# stm32f7.net
KiCad netlist of a schematic drawn in EAGLE
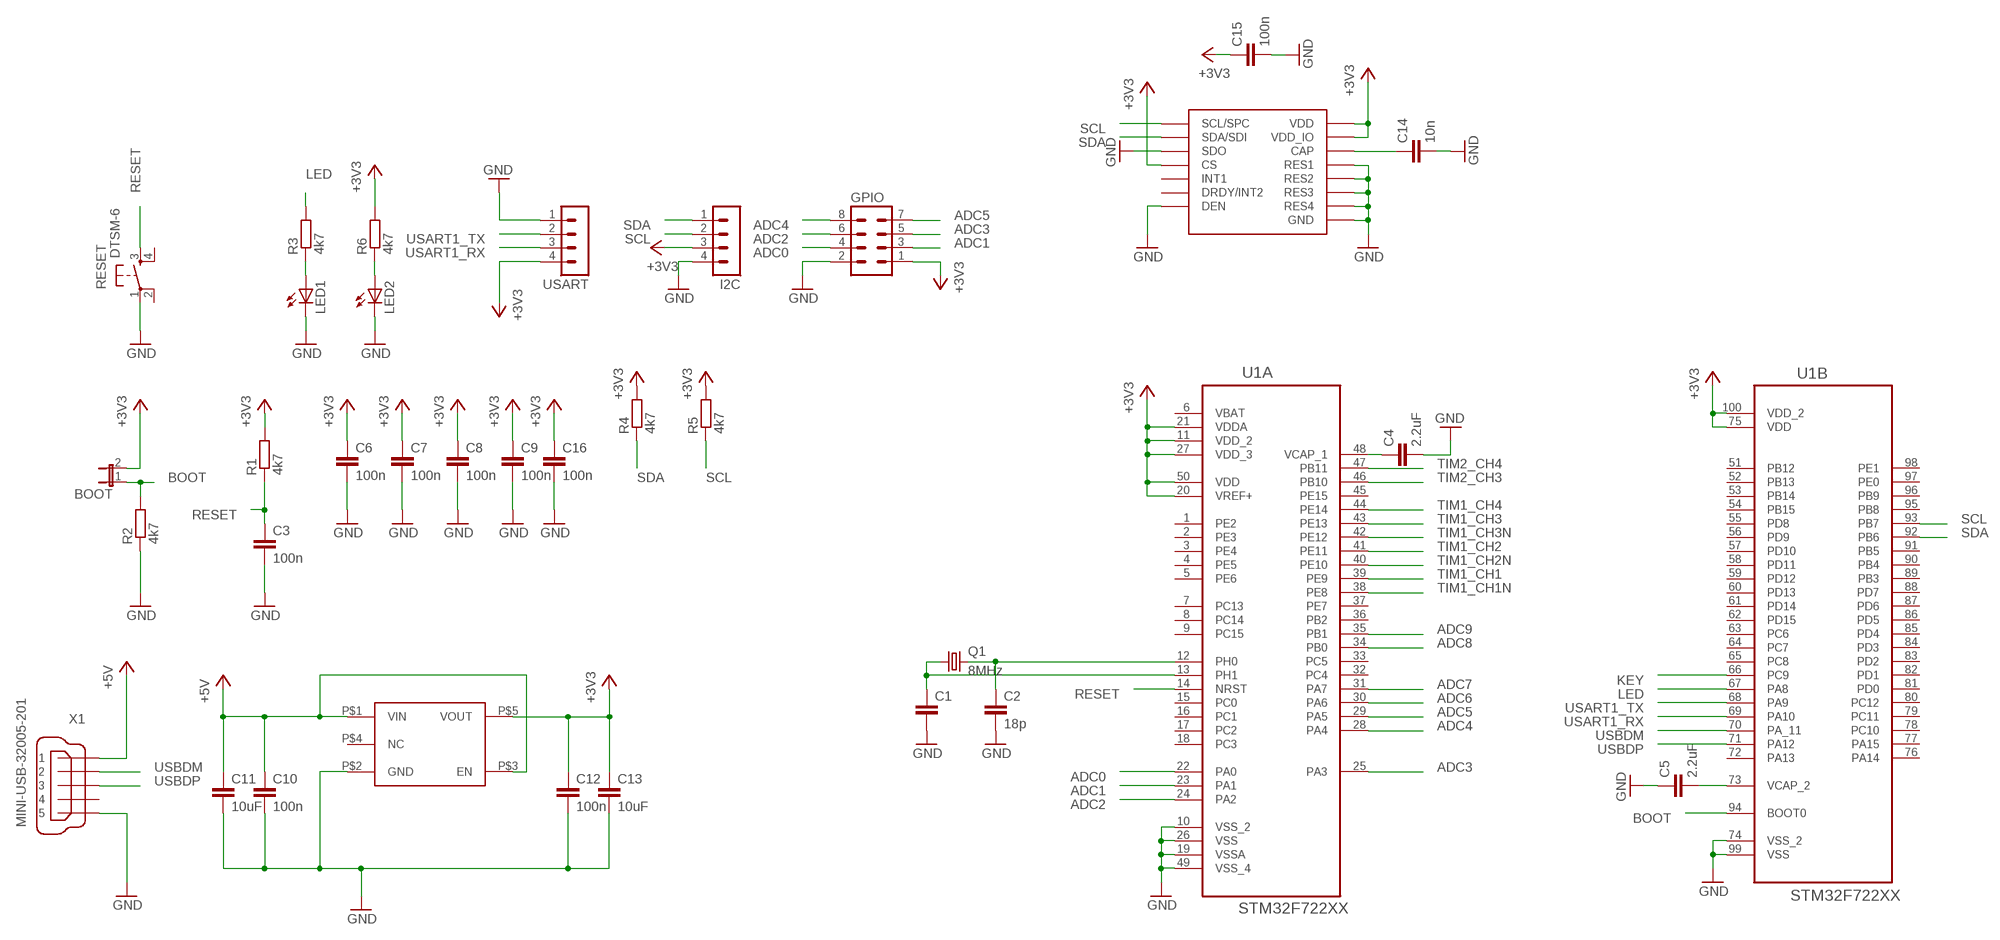
[diagram p0: schematic, sheet 1]

(export (version "E")
  (design (tool "Eeschema 10.0.6"))
  (components
    (comp (ref "BOOT")
      (value "JP1E")
      (footprint "eagle-import:JP1")
      (libsource (lib "eagle-import") (part "JP1E"))
    )
    (comp (ref "C1")
      (value "C-EUC0805")
      (footprint "eagle-import:C0805")
      (libsource (lib "eagle-import") (part "C-EUC0805"))
    )
    (comp (ref "C2")
      (value "18p")
      (footprint "eagle-import:C0805")
      (libsource (lib "eagle-import") (part "C-EUC0805"))
    )
    (comp (ref "C3")
      (value "100n")
      (footprint "eagle-import:C0805")
      (libsource (lib "eagle-import") (part "C-EUC0805"))
    )
    (comp (ref "C4")
      (value "2.2uF")
      (footprint "eagle-import:C0805")
      (libsource (lib "eagle-import") (part "C-EUC0805"))
    )
    (comp (ref "C5")
      (value "2.2uF")
      (footprint "eagle-import:C0805")
      (libsource (lib "eagle-import") (part "C-EUC0805"))
    )
    (comp (ref "C6")
      (value "100n")
      (footprint "eagle-import:C0805")
      (libsource (lib "eagle-import") (part "C-EUC0805"))
    )
    (comp (ref "C7")
      (value "100n")
      (footprint "eagle-import:C0805")
      (libsource (lib "eagle-import") (part "C-EUC0805"))
    )
    (comp (ref "C8")
      (value "100n")
      (footprint "eagle-import:C0805")
      (libsource (lib "eagle-import") (part "C-EUC0805"))
    )
    (comp (ref "C9")
      (value "100n")
      (footprint "eagle-import:C0805")
      (libsource (lib "eagle-import") (part "C-EUC0805"))
    )
    (comp (ref "C10")
      (value "100n")
      (footprint "eagle-import:C0805")
      (libsource (lib "eagle-import") (part "C-EUC0805"))
    )
    (comp (ref "C11")
      (value "10uF")
      (footprint "eagle-import:C0805")
      (libsource (lib "eagle-import") (part "C-EUC0805"))
    )
    (comp (ref "C12")
      (value "100n")
      (footprint "eagle-import:C0805")
      (libsource (lib "eagle-import") (part "C-EUC0805"))
    )
    (comp (ref "C13")
      (value "10uF")
      (footprint "eagle-import:C0805")
      (libsource (lib "eagle-import") (part "C-EUC0805"))
    )
    (comp (ref "C14")
      (value "10n")
      (footprint "eagle-import:C0805")
      (libsource (lib "eagle-import") (part "C-EUC0805"))
    )
    (comp (ref "C15")
      (value "100n")
      (footprint "eagle-import:C0805")
      (libsource (lib "eagle-import") (part "C-EUC0805"))
    )
    (comp (ref "C16")
      (value "100n")
      (footprint "eagle-import:C0805")
      (libsource (lib "eagle-import") (part "C-EUC0805"))
    )
    (comp (ref "GPIO")
      (value "MA04-2")
      (footprint "eagle-import:MA04-2")
      (libsource (lib "eagle-import") (part "MA04-2"))
    )
    (comp (ref "I2C")
      (value "MA04-1")
      (footprint "eagle-import:MA04-1")
      (libsource (lib "eagle-import") (part "MA04-1"))
    )
    (comp (ref "LED1")
      (value "LEDCHIPLED_1206")
      (footprint "eagle-import:CHIPLED_1206")
      (libsource (lib "eagle-import") (part "LEDCHIPLED_1206"))
    )
    (comp (ref "LED2")
      (value "LEDCHIPLED_1206")
      (footprint "eagle-import:CHIPLED_1206")
      (libsource (lib "eagle-import") (part "LEDCHIPLED_1206"))
    )
    (comp (ref "Q1")
      (value "8MHz")
      (footprint "eagle-import:CTS406")
      (libsource (lib "eagle-import") (part "CRYSTALCTS406"))
    )
    (comp (ref "R1")
      (value "4k7")
      (footprint "eagle-import:M0805")
      (libsource (lib "eagle-import") (part "R-EU_M0805"))
    )
    (comp (ref "R2")
      (value "4k7")
      (footprint "eagle-import:M0805")
      (libsource (lib "eagle-import") (part "R-EU_M0805"))
    )
    (comp (ref "R3")
      (value "4k7")
      (footprint "eagle-import:M0805")
      (libsource (lib "eagle-import") (part "R-EU_M0805"))
    )
    (comp (ref "R4")
      (value "4k7")
      (footprint "eagle-import:M0805")
      (libsource (lib "eagle-import") (part "R-EU_M0805"))
    )
    (comp (ref "R5")
      (value "4k7")
      (footprint "eagle-import:M0805")
      (libsource (lib "eagle-import") (part "R-EU_M0805"))
    )
    (comp (ref "R6")
      (value "4k7")
      (footprint "eagle-import:M0805")
      (libsource (lib "eagle-import") (part "R-EU_M0805"))
    )
    (comp (ref "RESET")
      (value "DTSM-6")
      (footprint "eagle-import:DTSM-6")
      (libsource (lib "eagle-import") (part "DTSM-6"))
    )
    (comp (ref "U$1")
      (value "MIC5504-3.3Y")
      (footprint "eagle-import:SOT23-5")
      (libsource (lib "eagle-import") (part "MIC5504-3.3Y"))
    )
    (comp (ref "U$2")
      (value "ST_L3GD20H")
      (footprint "eagle-import:ST_LGA16L")
      (libsource (lib "eagle-import") (part "ST_L3GD20H"))
    )
    (comp (ref "U1")
      (value "STM32F722XX")
      (footprint "eagle-import:QFP50P1600X1600X160-100N")
      (fields (field (name "MPN") "STM32F407VET6"))
      (libsource (lib "eagle-import") (part "STM32F722XX"))
    )
    (comp (ref "USART")
      (value "MA04-1")
      (footprint "eagle-import:MA04-1")
      (libsource (lib "eagle-import") (part "MA04-1"))
    )
    (comp (ref "X1")
      (value "MINI-USB-32005-201")
      (footprint "eagle-import:32005-201")
      (libsource (lib "eagle-import") (part "MINI-USB-32005-201"))
    )
  )
  (nets
    (net (code "1") (name "+3V3") (class "Default")
      (node (ref "BOOT") (pin "2") (pinfunction "2_2") (pintype "passive"))
      (node (ref "C12") (pin "1") (pinfunction "1_1") (pintype "passive"))
      (node (ref "C13") (pin "1") (pinfunction "1_1") (pintype "passive"))
      (node (ref "C15") (pin "1") (pinfunction "1_1") (pintype "passive"))
      (node (ref "C16") (pin "1") (pinfunction "1_1") (pintype "passive"))
      (node (ref "C6") (pin "1") (pinfunction "1_1") (pintype "passive"))
      (node (ref "C7") (pin "1") (pinfunction "1_1") (pintype "passive"))
      (node (ref "C8") (pin "1") (pinfunction "1_1") (pintype "passive"))
      (node (ref "C9") (pin "1") (pinfunction "1_1") (pintype "passive"))
      (node (ref "GPIO") (pin "1") (pinfunction "1_1") (pintype "passive"))
      (node (ref "I2C") (pin "3") (pinfunction "3_3") (pintype "passive"))
      (node (ref "R1") (pin "2") (pinfunction "2_2") (pintype "passive"))
      (node (ref "R4") (pin "2") (pinfunction "2_2") (pintype "passive"))
      (node (ref "R5") (pin "2") (pinfunction "2_2") (pintype "passive"))
      (node (ref "R6") (pin "2") (pinfunction "2_2") (pintype "passive"))
      (node (ref "U$1") (pin "P$5") (pinfunction "VOUT_P$5") (pintype "bidirectional"))
      (node (ref "U$2") (pin "P$1") (pinfunction "VDD_IO_P$1") (pintype "power_in"))
      (node (ref "U$2") (pin "P$16") (pinfunction "VDD_P$16") (pintype "power_in"))
      (node (ref "U$2") (pin "P$5") (pinfunction "CS_P$5") (pintype "bidirectional"))
      (node (ref "U1") (pin "100") (pinfunction "VDD_2_100") (pintype "power_in"))
      (node (ref "U1") (pin "11") (pinfunction "VDD_2_11") (pintype "power_in"))
      (node (ref "U1") (pin "20") (pinfunction "VREF+_20") (pintype "power_in"))
      (node (ref "U1") (pin "21") (pinfunction "VDDA_21") (pintype "power_in"))
      (node (ref "U1") (pin "27") (pinfunction "VDD_3_27") (pintype "power_in"))
      (node (ref "U1") (pin "50") (pinfunction "VDD_50") (pintype "power_in"))
      (node (ref "U1") (pin "75") (pinfunction "VDD_75") (pintype "power_in"))
      (node (ref "USART") (pin "4") (pinfunction "4_4") (pintype "passive"))
    )
    (net (code "2") (name "+5V") (class "Default")
      (node (ref "C10") (pin "1") (pinfunction "1_1") (pintype "passive"))
      (node (ref "C11") (pin "1") (pinfunction "1_1") (pintype "passive"))
      (node (ref "U$1") (pin "P$1") (pinfunction "VIN_P$1") (pintype "bidirectional"))
      (node (ref "U$1") (pin "P$3") (pinfunction "EN_P$3") (pintype "bidirectional"))
      (node (ref "X1") (pin "1") (pinfunction "1_1") (pintype "passive"))
    )
    (net (code "3") (name "/ADC0") (class "Default")
      (node (ref "GPIO") (pin "4") (pinfunction "4_4") (pintype "passive"))
      (node (ref "U1") (pin "22") (pinfunction "PA0_22") (pintype "bidirectional"))
    )
    (net (code "4") (name "/ADC1") (class "Default")
      (node (ref "GPIO") (pin "3") (pinfunction "3_3") (pintype "passive"))
      (node (ref "U1") (pin "23") (pinfunction "PA1_23") (pintype "bidirectional"))
    )
    (net (code "5") (name "/ADC2") (class "Default")
      (node (ref "GPIO") (pin "6") (pinfunction "6_6") (pintype "passive"))
      (node (ref "U1") (pin "24") (pinfunction "PA2_24") (pintype "bidirectional"))
    )
    (net (code "6") (name "/ADC3") (class "Default")
      (node (ref "GPIO") (pin "5") (pinfunction "5_5") (pintype "passive"))
      (node (ref "U1") (pin "25") (pinfunction "PA3_25") (pintype "bidirectional"))
    )
    (net (code "7") (name "/ADC4") (class "Default")
      (node (ref "GPIO") (pin "8") (pinfunction "8_8") (pintype "passive"))
      (node (ref "U1") (pin "28") (pinfunction "PA4_28") (pintype "bidirectional"))
    )
    (net (code "8") (name "/ADC5") (class "Default")
      (node (ref "GPIO") (pin "7") (pinfunction "7_7") (pintype "passive"))
      (node (ref "U1") (pin "29") (pinfunction "PA5_29") (pintype "bidirectional"))
    )
    (net (code "9") (name "/ADC6") (class "Default")
      (node (ref "U1") (pin "30") (pinfunction "PA6_30") (pintype "bidirectional"))
    )
    (net (code "10") (name "/ADC7") (class "Default")
      (node (ref "U1") (pin "31") (pinfunction "PA7_31") (pintype "bidirectional"))
    )
    (net (code "11") (name "/ADC8") (class "Default")
      (node (ref "U1") (pin "34") (pinfunction "PB0_34") (pintype "bidirectional"))
    )
    (net (code "12") (name "/ADC9") (class "Default")
      (node (ref "U1") (pin "35") (pinfunction "PB1_35") (pintype "bidirectional"))
    )
    (net (code "13") (name "/BOOT") (class "Default")
      (node (ref "BOOT") (pin "1") (pinfunction "1_1") (pintype "passive"))
      (node (ref "R2") (pin "2") (pinfunction "2_2") (pintype "passive"))
      (node (ref "U1") (pin "94") (pinfunction "BOOT0_94") (pintype "input"))
    )
    (net (code "14") (name "/KEY") (class "Default")
      (node (ref "U1") (pin "66") (pinfunction "PC9_66") (pintype "bidirectional"))
    )
    (net (code "15") (name "/LED") (class "Default")
      (node (ref "R3") (pin "2") (pinfunction "2_2") (pintype "passive"))
      (node (ref "U1") (pin "67") (pinfunction "PA8_67") (pintype "bidirectional"))
    )
    (net (code "16") (name "/RESET") (class "Default")
      (node (ref "C3") (pin "1") (pinfunction "1_1") (pintype "passive"))
      (node (ref "R1") (pin "1") (pinfunction "1_1") (pintype "passive"))
      (node (ref "RESET") (pin "3") (pinfunction "3_3") (pintype "passive"))
      (node (ref "U1") (pin "14") (pinfunction "NRST_14") (pintype "bidirectional"))
    )
    (net (code "17") (name "/SCL") (class "Default")
      (node (ref "I2C") (pin "2") (pinfunction "2_2") (pintype "passive"))
      (node (ref "R5") (pin "1") (pinfunction "1_1") (pintype "passive"))
      (node (ref "U$2") (pin "P$2") (pinfunction "SCL/SPC_P$2") (pintype "bidirectional"))
      (node (ref "U1") (pin "93") (pinfunction "PB7_93") (pintype "bidirectional"))
    )
    (net (code "18") (name "/SDA") (class "Default")
      (node (ref "I2C") (pin "1") (pinfunction "1_1") (pintype "passive"))
      (node (ref "R4") (pin "1") (pinfunction "1_1") (pintype "passive"))
      (node (ref "U$2") (pin "P$3") (pinfunction "SDA/SDI_P$3") (pintype "bidirectional"))
      (node (ref "U1") (pin "92") (pinfunction "PB6_92") (pintype "bidirectional"))
    )
    (net (code "19") (name "/TIM1_CH1") (class "Default")
      (node (ref "U1") (pin "39") (pinfunction "PE9_39") (pintype "bidirectional"))
    )
    (net (code "20") (name "/TIM1_CH1N") (class "Default")
      (node (ref "U1") (pin "38") (pinfunction "PE8_38") (pintype "bidirectional"))
    )
    (net (code "21") (name "/TIM1_CH2") (class "Default")
      (node (ref "U1") (pin "41") (pinfunction "PE11_41") (pintype "bidirectional"))
    )
    (net (code "22") (name "/TIM1_CH2N") (class "Default")
      (node (ref "U1") (pin "40") (pinfunction "PE10_40") (pintype "bidirectional"))
    )
    (net (code "23") (name "/TIM1_CH3") (class "Default")
      (node (ref "U1") (pin "43") (pinfunction "PE13_43") (pintype "bidirectional"))
    )
    (net (code "24") (name "/TIM1_CH3N") (class "Default")
      (node (ref "U1") (pin "42") (pinfunction "PE12_42") (pintype "bidirectional"))
    )
    (net (code "25") (name "/TIM1_CH4") (class "Default")
      (node (ref "U1") (pin "44") (pinfunction "PE14_44") (pintype "bidirectional"))
    )
    (net (code "26") (name "/TIM2_CH3") (class "Default")
      (node (ref "U1") (pin "46") (pinfunction "PB10_46") (pintype "bidirectional"))
    )
    (net (code "27") (name "/TIM2_CH4") (class "Default")
      (node (ref "U1") (pin "47") (pinfunction "PB11_47") (pintype "bidirectional"))
    )
    (net (code "28") (name "/USART1_RX") (class "Default")
      (node (ref "U1") (pin "69") (pinfunction "PA10_69") (pintype "bidirectional"))
      (node (ref "USART") (pin "3") (pinfunction "3_3") (pintype "passive"))
    )
    (net (code "29") (name "/USART1_TX") (class "Default")
      (node (ref "U1") (pin "68") (pinfunction "PA9_68") (pintype "bidirectional"))
      (node (ref "USART") (pin "2") (pinfunction "2_2") (pintype "passive"))
    )
    (net (code "30") (name "/USBDM") (class "Default")
      (node (ref "U1") (pin "70") (pinfunction "PA_11_70") (pintype "bidirectional"))
      (node (ref "X1") (pin "2") (pinfunction "2_2") (pintype "passive"))
    )
    (net (code "31") (name "/USBDP") (class "Default")
      (node (ref "U1") (pin "71") (pinfunction "PA12_71") (pintype "bidirectional"))
      (node (ref "X1") (pin "3") (pinfunction "3_3") (pintype "passive"))
    )
    (net (code "32") (name "/VBAT") (class "Default")
      (node (ref "U1") (pin "6") (pinfunction "VBAT_6") (pintype "power_in"))
    )
    (net (code "33") (name "GND") (class "Default")
      (node (ref "C1") (pin "2") (pinfunction "2_2") (pintype "passive"))
      (node (ref "C10") (pin "2") (pinfunction "2_2") (pintype "passive"))
      (node (ref "C11") (pin "2") (pinfunction "2_2") (pintype "passive"))
      (node (ref "C12") (pin "2") (pinfunction "2_2") (pintype "passive"))
      (node (ref "C13") (pin "2") (pinfunction "2_2") (pintype "passive"))
      (node (ref "C14") (pin "2") (pinfunction "2_2") (pintype "passive"))
      (node (ref "C15") (pin "2") (pinfunction "2_2") (pintype "passive"))
      (node (ref "C16") (pin "2") (pinfunction "2_2") (pintype "passive"))
      (node (ref "C2") (pin "2") (pinfunction "2_2") (pintype "passive"))
      (node (ref "C3") (pin "2") (pinfunction "2_2") (pintype "passive"))
      (node (ref "C4") (pin "2") (pinfunction "2_2") (pintype "passive"))
      (node (ref "C5") (pin "1") (pinfunction "1_1") (pintype "passive"))
      (node (ref "C6") (pin "2") (pinfunction "2_2") (pintype "passive"))
      (node (ref "C7") (pin "2") (pinfunction "2_2") (pintype "passive"))
      (node (ref "C8") (pin "2") (pinfunction "2_2") (pintype "passive"))
      (node (ref "C9") (pin "2") (pinfunction "2_2") (pintype "passive"))
      (node (ref "GPIO") (pin "2") (pinfunction "2_2") (pintype "passive"))
      (node (ref "I2C") (pin "4") (pinfunction "4_4") (pintype "passive"))
      (node (ref "LED1") (pin "C") (pinfunction "C_C") (pintype "passive"))
      (node (ref "LED2") (pin "C") (pinfunction "C_C") (pintype "passive"))
      (node (ref "R2") (pin "1") (pinfunction "1_1") (pintype "passive"))
      (node (ref "RESET") (pin "1") (pinfunction "1_1") (pintype "passive"))
      (node (ref "U$1") (pin "P$2") (pinfunction "GND_P$2") (pintype "bidirectional"))
      (node (ref "U$2") (pin "P$10") (pinfunction "RES2_P$10") (pintype "bidirectional"))
      (node (ref "U$2") (pin "P$11") (pinfunction "RES3_P$11") (pintype "bidirectional"))
      (node (ref "U$2") (pin "P$12") (pinfunction "GND_P$12") (pintype "power_in"))
      (node (ref "U$2") (pin "P$13") (pinfunction "GND_P$13") (pintype "power_in"))
      (node (ref "U$2") (pin "P$15") (pinfunction "RES4_P$15") (pintype "bidirectional"))
      (node (ref "U$2") (pin "P$4") (pinfunction "SDO_P$4") (pintype "bidirectional"))
      (node (ref "U$2") (pin "P$8") (pinfunction "DEN_P$8") (pintype "bidirectional"))
      (node (ref "U$2") (pin "P$9") (pinfunction "RES1_P$9") (pintype "bidirectional"))
      (node (ref "U1") (pin "10") (pinfunction "VSS_2_10") (pintype "passive"))
      (node (ref "U1") (pin "19") (pinfunction "VSSA_19") (pintype "passive"))
      (node (ref "U1") (pin "26") (pinfunction "VSS_26") (pintype "passive"))
      (node (ref "U1") (pin "49") (pinfunction "VSS_4_49") (pintype "power_in"))
      (node (ref "U1") (pin "74") (pinfunction "VSS_2_74") (pintype "passive"))
      (node (ref "U1") (pin "99") (pinfunction "VSS_99") (pintype "passive"))
      (node (ref "USART") (pin "1") (pinfunction "1_1") (pintype "passive"))
      (node (ref "X1") (pin "5") (pinfunction "5_5") (pintype "passive"))
    )
    (net (code "34") (name "Net-(LED1-PadA)") (class "Default")
      (node (ref "LED1") (pin "A") (pinfunction "A_A") (pintype "passive"))
      (node (ref "R3") (pin "1") (pinfunction "1_1") (pintype "passive"))
    )
    (net (code "35") (name "Net-(LED2-PadA)") (class "Default")
      (node (ref "LED2") (pin "A") (pinfunction "A_A") (pintype "passive"))
      (node (ref "R6") (pin "1") (pinfunction "1_1") (pintype "passive"))
    )
    (net (code "36") (name "Net-(Q1-2)") (class "Default")
      (node (ref "C2") (pin "1") (pinfunction "1_1") (pintype "passive"))
      (node (ref "Q1") (pin "3") (pinfunction "2_3") (pintype "passive"))
      (node (ref "U1") (pin "12") (pinfunction "PH0_12") (pintype "bidirectional"))
    )
    (net (code "37") (name "Net-(U$2-CAP)") (class "Default")
      (node (ref "C14") (pin "1") (pinfunction "1_1") (pintype "passive"))
      (node (ref "U$2") (pin "P$14") (pinfunction "CAP_P$14") (pintype "bidirectional"))
    )
    (net (code "38") (name "Net-(U1A-PH1)") (class "Default")
      (node (ref "C1") (pin "1") (pinfunction "1_1") (pintype "passive"))
      (node (ref "Q1") (pin "1") (pinfunction "1_1") (pintype "passive"))
      (node (ref "U1") (pin "13") (pinfunction "PH1_13") (pintype "bidirectional"))
    )
    (net (code "39") (name "Net-(U1A-VCAP_1)") (class "Default")
      (node (ref "C4") (pin "1") (pinfunction "1_1") (pintype "passive"))
      (node (ref "U1") (pin "48") (pinfunction "VCAP_1_48") (pintype "power_in"))
    )
    (net (code "40") (name "Net-(U1B-VCAP_2)") (class "Default")
      (node (ref "C5") (pin "2") (pinfunction "2_2") (pintype "passive"))
      (node (ref "U1") (pin "73") (pinfunction "VCAP_2_73") (pintype "power_in"))
    )
    (net (code "41") (name "unconnected-(RESET-Pad2)") (class "Default")
      (node (ref "RESET") (pin "2") (pinfunction "2_2") (pintype "passive"))
    )
    (net (code "42") (name "unconnected-(RESET-Pad4)") (class "Default")
      (node (ref "RESET") (pin "4") (pinfunction "4_4") (pintype "passive"))
    )
    (net (code "43") (name "unconnected-(U$1-NC-PadP$4)") (class "Default")
      (node (ref "U$1") (pin "P$4") (pinfunction "NC_P$4") (pintype "bidirectional"))
    )
    (net (code "44") (name "unconnected-(U$2-DRDY{slash}INT2-PadP$6)") (class "Default")
      (node (ref "U$2") (pin "P$6") (pinfunction "DRDY/INT2_P$6") (pintype "bidirectional"))
    )
    (net (code "45") (name "unconnected-(U$2-INT1-PadP$7)") (class "Default")
      (node (ref "U$2") (pin "P$7") (pinfunction "INT1_P$7") (pintype "bidirectional"))
    )
    (net (code "46") (name "unconnected-(U1A-PB2-Pad36)") (class "Default")
      (node (ref "U1") (pin "36") (pinfunction "PB2_36") (pintype "bidirectional"))
    )
    (net (code "47") (name "unconnected-(U1A-PC0-Pad15)") (class "Default")
      (node (ref "U1") (pin "15") (pinfunction "PC0_15") (pintype "bidirectional"))
    )
    (net (code "48") (name "unconnected-(U1A-PC1-Pad16)") (class "Default")
      (node (ref "U1") (pin "16") (pinfunction "PC1_16") (pintype "bidirectional"))
    )
    (net (code "49") (name "unconnected-(U1A-PC2-Pad17)") (class "Default")
      (node (ref "U1") (pin "17") (pinfunction "PC2_17") (pintype "bidirectional"))
    )
    (net (code "50") (name "unconnected-(U1A-PC3-Pad18)") (class "Default")
      (node (ref "U1") (pin "18") (pinfunction "PC3_18") (pintype "bidirectional"))
    )
    (net (code "51") (name "unconnected-(U1A-PC4-Pad32)") (class "Default")
      (node (ref "U1") (pin "32") (pinfunction "PC4_32") (pintype "bidirectional"))
    )
    (net (code "52") (name "unconnected-(U1A-PC5-Pad33)") (class "Default")
      (node (ref "U1") (pin "33") (pinfunction "PC5_33") (pintype "bidirectional"))
    )
    (net (code "53") (name "unconnected-(U1A-PC13-Pad7)") (class "Default")
      (node (ref "U1") (pin "7") (pinfunction "PC13_7") (pintype "bidirectional"))
    )
    (net (code "54") (name "unconnected-(U1A-PC14-Pad8)") (class "Default")
      (node (ref "U1") (pin "8") (pinfunction "PC14_8") (pintype "bidirectional"))
    )
    (net (code "55") (name "unconnected-(U1A-PC15-Pad9)") (class "Default")
      (node (ref "U1") (pin "9") (pinfunction "PC15_9") (pintype "bidirectional"))
    )
    (net (code "56") (name "unconnected-(U1A-PE2-Pad1)") (class "Default")
      (node (ref "U1") (pin "1") (pinfunction "PE2_1") (pintype "bidirectional"))
    )
    (net (code "57") (name "unconnected-(U1A-PE3-Pad2)") (class "Default")
      (node (ref "U1") (pin "2") (pinfunction "PE3_2") (pintype "bidirectional"))
    )
    (net (code "58") (name "unconnected-(U1A-PE4-Pad3)") (class "Default")
      (node (ref "U1") (pin "3") (pinfunction "PE4_3") (pintype "bidirectional"))
    )
    (net (code "59") (name "unconnected-(U1A-PE5-Pad4)") (class "Default")
      (node (ref "U1") (pin "4") (pinfunction "PE5_4") (pintype "bidirectional"))
    )
    (net (code "60") (name "unconnected-(U1A-PE6-Pad5)") (class "Default")
      (node (ref "U1") (pin "5") (pinfunction "PE6_5") (pintype "bidirectional"))
    )
    (net (code "61") (name "unconnected-(U1A-PE7-Pad37)") (class "Default")
      (node (ref "U1") (pin "37") (pinfunction "PE7_37") (pintype "bidirectional"))
    )
    (net (code "62") (name "unconnected-(U1A-PE15-Pad45)") (class "Default")
      (node (ref "U1") (pin "45") (pinfunction "PE15_45") (pintype "bidirectional"))
    )
    (net (code "63") (name "unconnected-(U1B-PA13-Pad72)") (class "Default")
      (node (ref "U1") (pin "72") (pinfunction "PA13_72") (pintype "bidirectional"))
    )
    (net (code "64") (name "unconnected-(U1B-PA14-Pad76)") (class "Default")
      (node (ref "U1") (pin "76") (pinfunction "PA14_76") (pintype "bidirectional"))
    )
    (net (code "65") (name "unconnected-(U1B-PA15-Pad77)") (class "Default")
      (node (ref "U1") (pin "77") (pinfunction "PA15_77") (pintype "bidirectional"))
    )
    (net (code "66") (name "unconnected-(U1B-PB3-Pad89)") (class "Default")
      (node (ref "U1") (pin "89") (pinfunction "PB3_89") (pintype "bidirectional"))
    )
    (net (code "67") (name "unconnected-(U1B-PB4-Pad90)") (class "Default")
      (node (ref "U1") (pin "90") (pinfunction "PB4_90") (pintype "bidirectional"))
    )
    (net (code "68") (name "unconnected-(U1B-PB5-Pad91)") (class "Default")
      (node (ref "U1") (pin "91") (pinfunction "PB5_91") (pintype "bidirectional"))
    )
    (net (code "69") (name "unconnected-(U1B-PB8-Pad95)") (class "Default")
      (node (ref "U1") (pin "95") (pinfunction "PB8_95") (pintype "bidirectional"))
    )
    (net (code "70") (name "unconnected-(U1B-PB9-Pad96)") (class "Default")
      (node (ref "U1") (pin "96") (pinfunction "PB9_96") (pintype "bidirectional"))
    )
    (net (code "71") (name "unconnected-(U1B-PB12-Pad51)") (class "Default")
      (node (ref "U1") (pin "51") (pinfunction "PB12_51") (pintype "bidirectional"))
    )
    (net (code "72") (name "unconnected-(U1B-PB13-Pad52)") (class "Default")
      (node (ref "U1") (pin "52") (pinfunction "PB13_52") (pintype "bidirectional"))
    )
    (net (code "73") (name "unconnected-(U1B-PB14-Pad53)") (class "Default")
      (node (ref "U1") (pin "53") (pinfunction "PB14_53") (pintype "bidirectional"))
    )
    (net (code "74") (name "unconnected-(U1B-PB15-Pad54)") (class "Default")
      (node (ref "U1") (pin "54") (pinfunction "PB15_54") (pintype "bidirectional"))
    )
    (net (code "75") (name "unconnected-(U1B-PC6-Pad63)") (class "Default")
      (node (ref "U1") (pin "63") (pinfunction "PC6_63") (pintype "bidirectional"))
    )
    (net (code "76") (name "unconnected-(U1B-PC7-Pad64)") (class "Default")
      (node (ref "U1") (pin "64") (pinfunction "PC7_64") (pintype "bidirectional"))
    )
    (net (code "77") (name "unconnected-(U1B-PC8-Pad65)") (class "Default")
      (node (ref "U1") (pin "65") (pinfunction "PC8_65") (pintype "bidirectional"))
    )
    (net (code "78") (name "unconnected-(U1B-PC10-Pad78)") (class "Default")
      (node (ref "U1") (pin "78") (pinfunction "PC10_78") (pintype "bidirectional"))
    )
    (net (code "79") (name "unconnected-(U1B-PC11-Pad79)") (class "Default")
      (node (ref "U1") (pin "79") (pinfunction "PC11_79") (pintype "bidirectional"))
    )
    (net (code "80") (name "unconnected-(U1B-PC12-Pad80)") (class "Default")
      (node (ref "U1") (pin "80") (pinfunction "PC12_80") (pintype "bidirectional"))
    )
    (net (code "81") (name "unconnected-(U1B-PD0-Pad81)") (class "Default")
      (node (ref "U1") (pin "81") (pinfunction "PD0_81") (pintype "bidirectional"))
    )
    (net (code "82") (name "unconnected-(U1B-PD1-Pad82)") (class "Default")
      (node (ref "U1") (pin "82") (pinfunction "PD1_82") (pintype "bidirectional"))
    )
    (net (code "83") (name "unconnected-(U1B-PD2-Pad83)") (class "Default")
      (node (ref "U1") (pin "83") (pinfunction "PD2_83") (pintype "bidirectional"))
    )
    (net (code "84") (name "unconnected-(U1B-PD3-Pad84)") (class "Default")
      (node (ref "U1") (pin "84") (pinfunction "PD3_84") (pintype "bidirectional"))
    )
    (net (code "85") (name "unconnected-(U1B-PD4-Pad85)") (class "Default")
      (node (ref "U1") (pin "85") (pinfunction "PD4_85") (pintype "bidirectional"))
    )
    (net (code "86") (name "unconnected-(U1B-PD5-Pad86)") (class "Default")
      (node (ref "U1") (pin "86") (pinfunction "PD5_86") (pintype "bidirectional"))
    )
    (net (code "87") (name "unconnected-(U1B-PD6-Pad87)") (class "Default")
      (node (ref "U1") (pin "87") (pinfunction "PD6_87") (pintype "bidirectional"))
    )
    (net (code "88") (name "unconnected-(U1B-PD7-Pad88)") (class "Default")
      (node (ref "U1") (pin "88") (pinfunction "PD7_88") (pintype "bidirectional"))
    )
    (net (code "89") (name "unconnected-(U1B-PD8-Pad55)") (class "Default")
      (node (ref "U1") (pin "55") (pinfunction "PD8_55") (pintype "bidirectional"))
    )
    (net (code "90") (name "unconnected-(U1B-PD9-Pad56)") (class "Default")
      (node (ref "U1") (pin "56") (pinfunction "PD9_56") (pintype "bidirectional"))
    )
    (net (code "91") (name "unconnected-(U1B-PD10-Pad57)") (class "Default")
      (node (ref "U1") (pin "57") (pinfunction "PD10_57") (pintype "bidirectional"))
    )
    (net (code "92") (name "unconnected-(U1B-PD11-Pad58)") (class "Default")
      (node (ref "U1") (pin "58") (pinfunction "PD11_58") (pintype "bidirectional"))
    )
    (net (code "93") (name "unconnected-(U1B-PD12-Pad59)") (class "Default")
      (node (ref "U1") (pin "59") (pinfunction "PD12_59") (pintype "bidirectional"))
    )
    (net (code "94") (name "unconnected-(U1B-PD13-Pad60)") (class "Default")
      (node (ref "U1") (pin "60") (pinfunction "PD13_60") (pintype "bidirectional"))
    )
    (net (code "95") (name "unconnected-(U1B-PD14-Pad61)") (class "Default")
      (node (ref "U1") (pin "61") (pinfunction "PD14_61") (pintype "bidirectional"))
    )
    (net (code "96") (name "unconnected-(U1B-PD15-Pad62)") (class "Default")
      (node (ref "U1") (pin "62") (pinfunction "PD15_62") (pintype "bidirectional"))
    )
    (net (code "97") (name "unconnected-(U1B-PE0-Pad97)") (class "Default")
      (node (ref "U1") (pin "97") (pinfunction "PE0_97") (pintype "bidirectional"))
    )
    (net (code "98") (name "unconnected-(U1B-PE1-Pad98)") (class "Default")
      (node (ref "U1") (pin "98") (pinfunction "PE1_98") (pintype "bidirectional"))
    )
    (net (code "99") (name "unconnected-(X1-Pad4)") (class "Default")
      (node (ref "X1") (pin "4") (pinfunction "4_4") (pintype "passive"))
    )
  )
)
